# ESP-XBee.net
KiCad netlist of a schematic drawn in EAGLE
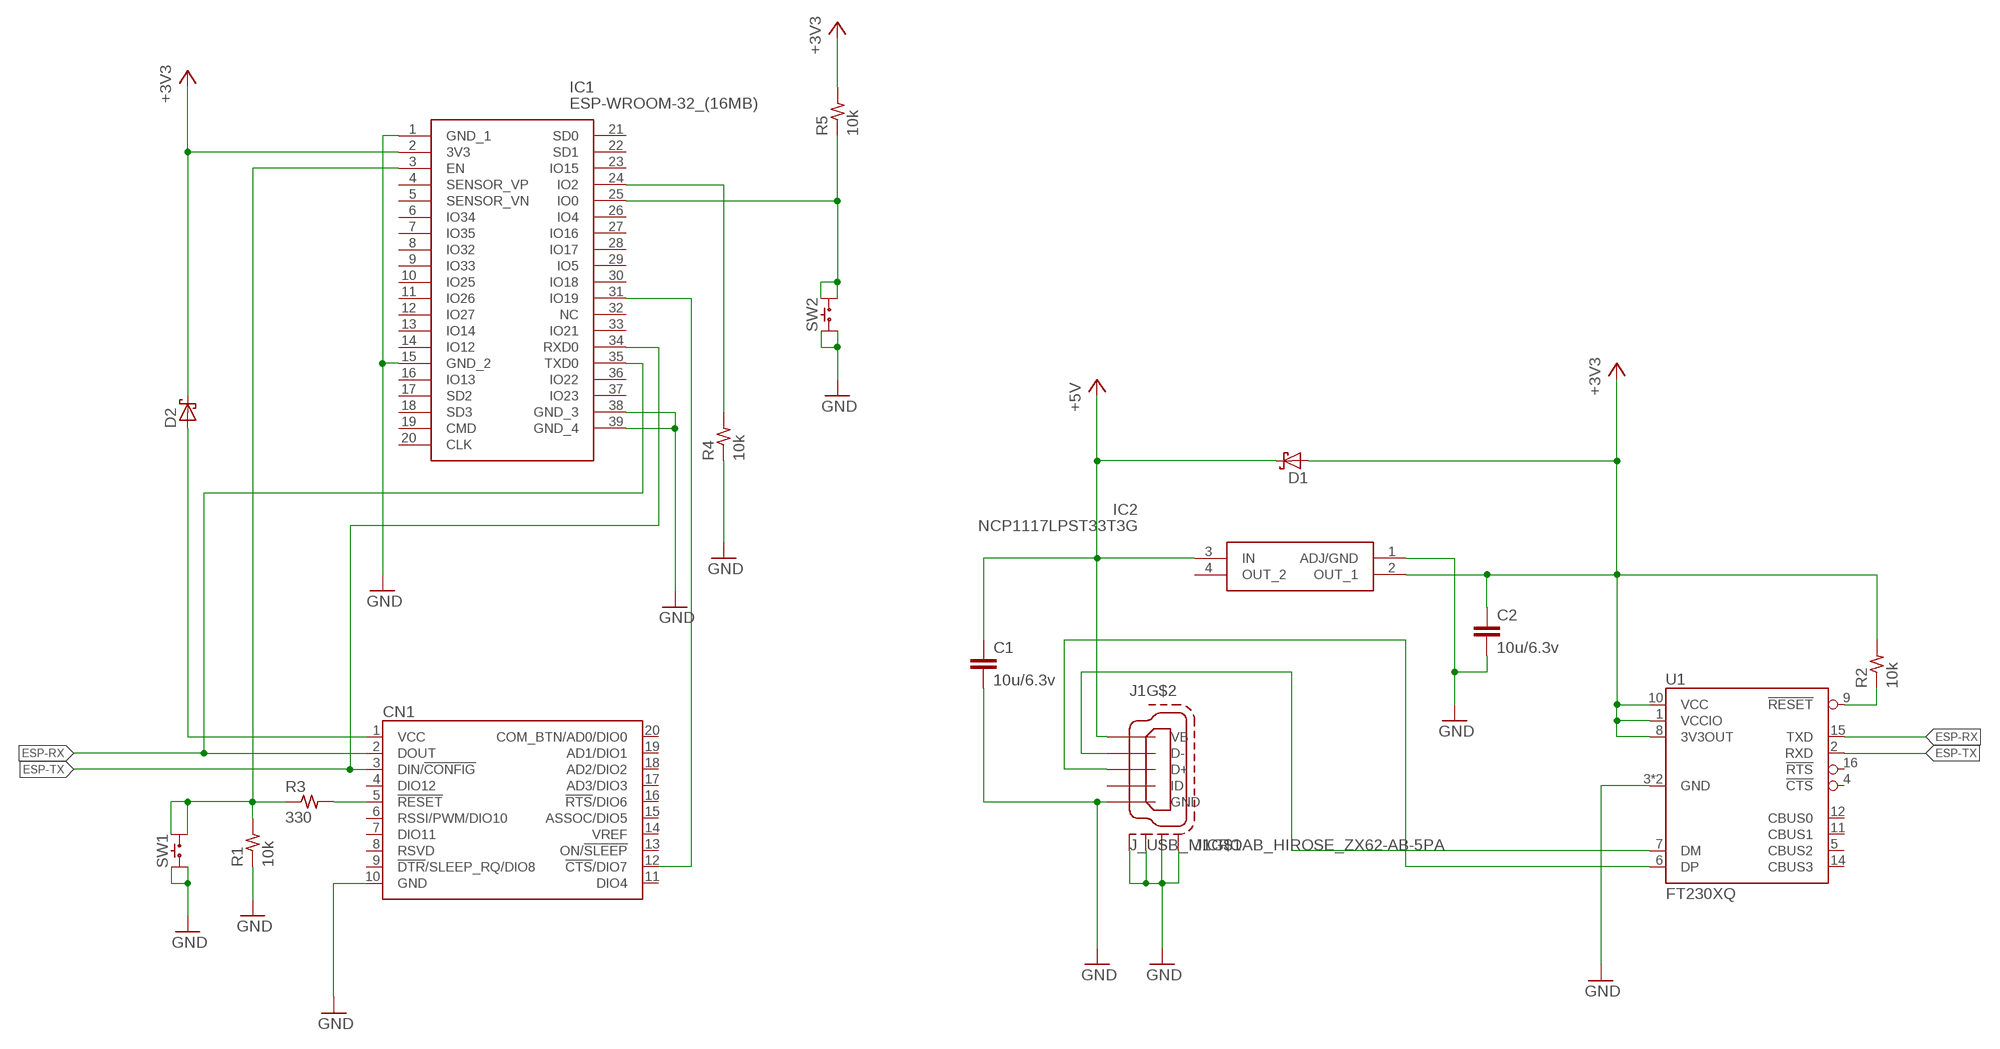
[diagram p0: schematic, sheet 1]

(export (version "E")
  (design (tool "Eeschema 10.0.6"))
  (components
    (comp (ref "C1")
      (value "10u/6.3v")
      (footprint "eagle-import:1005")
      (libsource (lib "eagle-import") (part "C1005"))
    )
    (comp (ref "C2")
      (value "10u/6.3v")
      (footprint "eagle-import:1005")
      (libsource (lib "eagle-import") (part "C1005"))
    )
    (comp (ref "CN1")
      (value "XBEE-TH")
      (footprint "eagle-import:XBEE-TH")
      (libsource (lib "eagle-import") (part "XBEE-TH"))
    )
    (comp (ref "D1")
      (value "SBD-SOD523")
      (footprint "eagle-import:SOD523")
      (libsource (lib "eagle-import") (part "SBD-SOD523"))
    )
    (comp (ref "D2")
      (value "SBD-SOD523")
      (footprint "eagle-import:SOD523")
      (libsource (lib "eagle-import") (part "SBD-SOD523"))
    )
    (comp (ref "IC1")
      (value "ESP-WROOM-32_(16MB)")
      (footprint "eagle-import:ESP32SOLO1")
      (fields (field (name "MANUFACTURER_PART_NUMBER") "ESP-WROOM-32 (16MB)"))
      (libsource (lib "eagle-import") (part "ESP-WROOM-32_(16MB)"))
    )
    (comp (ref "IC2")
      (value "NCP1117LPST33T3G")
      (footprint "eagle-import:SOT230P700X180-4N")
      (fields (field (name "RS_PART_NUMBER") "8022137P"))
      (libsource (lib "eagle-import") (part "NCP1117LPST33T3G"))
    )
    (comp (ref "J1")
      (value "J_USB_MICROAB_HIROSE_ZX62-AB-5PA")
      (footprint "eagle-import:J_USB_MICROAB_HIROSE_ZX62-AB-5PA")
      (libsource (lib "eagle-import") (part "J_USB_MICROAB_HIROSE_ZX62-AB-5PA"))
    )
    (comp (ref "R1")
      (value "10k")
      (footprint "eagle-import:1005")
      (libsource (lib "eagle-import") (part "R1005"))
    )
    (comp (ref "R2")
      (value "10k")
      (footprint "eagle-import:1005")
      (libsource (lib "eagle-import") (part "R1005"))
    )
    (comp (ref "R3")
      (value "330")
      (footprint "eagle-import:1005")
      (libsource (lib "eagle-import") (part "R1005"))
    )
    (comp (ref "R4")
      (value "10k")
      (footprint "eagle-import:1005")
      (libsource (lib "eagle-import") (part "R1005"))
    )
    (comp (ref "R5")
      (value "10k")
      (footprint "eagle-import:1005")
      (libsource (lib "eagle-import") (part "R1005"))
    )
    (comp (ref "SW1")
      (value "SKRP")
      (footprint "eagle-import:SKRP")
      (libsource (lib "eagle-import") (part "SKRP"))
    )
    (comp (ref "SW2")
      (value "SKRP")
      (footprint "eagle-import:SKRP")
      (libsource (lib "eagle-import") (part "SKRP"))
    )
    (comp (ref "U1")
      (value "FT230XQ")
      (footprint "eagle-import:QFN16-0.65-NOPAD")
      (libsource (lib "eagle-import") (part "FT230XQ"))
    )
  )
  (nets
    (net (code "1") (name "+3V3") (class "Default")
      (node (ref "C2") (pin "1") (pinfunction "1_1") (pintype "passive"))
      (node (ref "D1") (pin "A") (pinfunction "A_A") (pintype "passive"))
      (node (ref "D2") (pin "K") (pinfunction "K_K") (pintype "passive"))
      (node (ref "IC1") (pin "2") (pinfunction "3V3_2") (pintype "bidirectional"))
      (node (ref "IC2") (pin "2") (pinfunction "OUT_1_2") (pintype "output"))
      (node (ref "R2") (pin "2") (pinfunction "2_2") (pintype "passive"))
      (node (ref "R5") (pin "2") (pinfunction "2_2") (pintype "passive"))
      (node (ref "U1") (pin "1") (pinfunction "VCCIO_1") (pintype "bidirectional"))
      (node (ref "U1") (pin "10") (pinfunction "VCC_10") (pintype "bidirectional"))
      (node (ref "U1") (pin "8") (pinfunction "3V3OUT_8") (pintype "bidirectional"))
    )
    (net (code "2") (name "+5V") (class "Default")
      (node (ref "C1") (pin "1") (pinfunction "1_1") (pintype "passive"))
      (node (ref "D1") (pin "K") (pinfunction "K_K") (pintype "passive"))
      (node (ref "IC2") (pin "3") (pinfunction "IN_3") (pintype "input"))
      (node (ref "J1") (pin "P$1") (pinfunction "VB_P$1") (pintype "passive"))
    )
    (net (code "3") (name "ESP-RX") (class "Default")
      (node (ref "CN1") (pin "2") (pinfunction "DOUT_2") (pintype "bidirectional"))
      (node (ref "IC1") (pin "35") (pinfunction "TXD0_35") (pintype "bidirectional"))
      (node (ref "U1") (pin "15") (pinfunction "TXD_15") (pintype "bidirectional"))
    )
    (net (code "4") (name "ESP-TX") (class "Default")
      (node (ref "CN1") (pin "3") (pinfunction "DIN/~{CONFIG}_3") (pintype "bidirectional"))
      (node (ref "IC1") (pin "34") (pinfunction "RXD0_34") (pintype "bidirectional"))
      (node (ref "U1") (pin "2") (pinfunction "RXD_2") (pintype "bidirectional"))
    )
    (net (code "5") (name "GND") (class "Default")
      (node (ref "C1") (pin "2") (pinfunction "2_2") (pintype "passive"))
      (node (ref "C2") (pin "2") (pinfunction "2_2") (pintype "passive"))
      (node (ref "CN1") (pin "10") (pinfunction "GND_10") (pintype "bidirectional"))
      (node (ref "IC1") (pin "1") (pinfunction "GND_1_1") (pintype "bidirectional"))
      (node (ref "IC1") (pin "15") (pinfunction "GND_2_15") (pintype "bidirectional"))
      (node (ref "IC1") (pin "38") (pinfunction "GND_3_38") (pintype "bidirectional"))
      (node (ref "IC1") (pin "39") (pinfunction "GND_4_39") (pintype "bidirectional"))
      (node (ref "IC2") (pin "1") (pinfunction "ADJ/GND_1") (pintype "power_in"))
      (node (ref "J1") (pin "P$5") (pinfunction "GND_P$5") (pintype "passive"))
      (node (ref "J1") (pin "SHIELD1") (pinfunction "S1_SHIELD1") (pintype "passive"))
      (node (ref "J1") (pin "SHIELD2") (pinfunction "S2_SHIELD2") (pintype "passive"))
      (node (ref "J1") (pin "SHIELD3") (pinfunction "S3_SHIELD3") (pintype "passive"))
      (node (ref "J1") (pin "SHIELD4") (pinfunction "S4_SHIELD4") (pintype "passive"))
      (node (ref "R1") (pin "1") (pinfunction "1_1") (pintype "passive"))
      (node (ref "R4") (pin "1") (pinfunction "1_1") (pintype "passive"))
      (node (ref "SW1") (pin "A1") (pinfunction "A1_A1") (pintype "passive"))
      (node (ref "SW1") (pin "A2") (pinfunction "A2_A2") (pintype "passive"))
      (node (ref "SW2") (pin "A1") (pinfunction "A1_A1") (pintype "passive"))
      (node (ref "SW2") (pin "A2") (pinfunction "A2_A2") (pintype "passive"))
      (node (ref "U1") (pin "13") (pinfunction "GND_13") (pintype "bidirectional"))
      (node (ref "U1") (pin "3") (pinfunction "GND_3") (pintype "bidirectional"))
    )
    (net (code "6") (name "Net-(CN1-VCC)") (class "Default")
      (node (ref "CN1") (pin "1") (pinfunction "VCC_1") (pintype "bidirectional"))
      (node (ref "D2") (pin "A") (pinfunction "A_A") (pintype "passive"))
    )
    (net (code "7") (name "Net-(CN1-~{CTS}{slash}DIO7)") (class "Default")
      (node (ref "CN1") (pin "12") (pinfunction "~{CTS}/DIO7_12") (pintype "bidirectional"))
      (node (ref "IC1") (pin "31") (pinfunction "IO19_31") (pintype "bidirectional"))
    )
    (net (code "8") (name "Net-(CN1-~{RESET})") (class "Default")
      (node (ref "CN1") (pin "5") (pinfunction "~{RESET}_5") (pintype "bidirectional"))
      (node (ref "R3") (pin "2") (pinfunction "2_2") (pintype "passive"))
    )
    (net (code "9") (name "Net-(IC1-EN)") (class "Default")
      (node (ref "IC1") (pin "3") (pinfunction "EN_3") (pintype "bidirectional"))
      (node (ref "R1") (pin "2") (pinfunction "2_2") (pintype "passive"))
      (node (ref "R3") (pin "1") (pinfunction "1_1") (pintype "passive"))
      (node (ref "SW1") (pin "B1") (pinfunction "B1_B1") (pintype "passive"))
      (node (ref "SW1") (pin "B2") (pinfunction "B2_B2") (pintype "passive"))
    )
    (net (code "10") (name "Net-(IC1-IO0)") (class "Default")
      (node (ref "IC1") (pin "25") (pinfunction "IO0_25") (pintype "bidirectional"))
      (node (ref "R5") (pin "1") (pinfunction "1_1") (pintype "passive"))
      (node (ref "SW2") (pin "B1") (pinfunction "B1_B1") (pintype "passive"))
      (node (ref "SW2") (pin "B2") (pinfunction "B2_B2") (pintype "passive"))
    )
    (net (code "11") (name "Net-(IC1-IO2)") (class "Default")
      (node (ref "IC1") (pin "24") (pinfunction "IO2_24") (pintype "bidirectional"))
      (node (ref "R4") (pin "2") (pinfunction "2_2") (pintype "passive"))
    )
    (net (code "12") (name "Net-(J1B-D+)") (class "Default")
      (node (ref "J1") (pin "P$3") (pinfunction "D+_P$3") (pintype "passive"))
      (node (ref "U1") (pin "6") (pinfunction "DP_6") (pintype "bidirectional"))
    )
    (net (code "13") (name "Net-(J1B-D-)") (class "Default")
      (node (ref "J1") (pin "P$2") (pinfunction "D-_P$2") (pintype "passive"))
      (node (ref "U1") (pin "7") (pinfunction "DM_7") (pintype "bidirectional"))
    )
    (net (code "14") (name "Net-(U1-~{RESET})") (class "Default")
      (node (ref "R2") (pin "1") (pinfunction "1_1") (pintype "passive"))
      (node (ref "U1") (pin "9") (pinfunction "~{RESET}_9") (pintype "bidirectional"))
    )
    (net (code "15") (name "unconnected-(CN1-AD1{slash}DIO1-Pad19)") (class "Default")
      (node (ref "CN1") (pin "19") (pinfunction "AD1/DIO1_19") (pintype "bidirectional"))
    )
    (net (code "16") (name "unconnected-(CN1-AD2{slash}DIO2-Pad18)") (class "Default")
      (node (ref "CN1") (pin "18") (pinfunction "AD2/DIO2_18") (pintype "bidirectional"))
    )
    (net (code "17") (name "unconnected-(CN1-AD3{slash}DIO3-Pad17)") (class "Default")
      (node (ref "CN1") (pin "17") (pinfunction "AD3/DIO3_17") (pintype "bidirectional"))
    )
    (net (code "18") (name "unconnected-(CN1-ASSOC{slash}DIO5-Pad15)") (class "Default")
      (node (ref "CN1") (pin "15") (pinfunction "ASSOC/DIO5_15") (pintype "bidirectional"))
    )
    (net (code "19") (name "unconnected-(CN1-COM_BTN{slash}AD0{slash}DIO0-Pad20)") (class "Default")
      (node (ref "CN1") (pin "20") (pinfunction "COM_BTN/AD0/DIO0_20") (pintype "bidirectional"))
    )
    (net (code "20") (name "unconnected-(CN1-DIO4-Pad11)") (class "Default")
      (node (ref "CN1") (pin "11") (pinfunction "DIO4_11") (pintype "bidirectional"))
    )
    (net (code "21") (name "unconnected-(CN1-DIO11-Pad7)") (class "Default")
      (node (ref "CN1") (pin "7") (pinfunction "DIO11_7") (pintype "bidirectional"))
    )
    (net (code "22") (name "unconnected-(CN1-DIO12-Pad4)") (class "Default")
      (node (ref "CN1") (pin "4") (pinfunction "DIO12_4") (pintype "bidirectional"))
    )
    (net (code "23") (name "unconnected-(CN1-ON{slash}~{SLEEP}-Pad13)") (class "Default")
      (node (ref "CN1") (pin "13") (pinfunction "ON/~{SLEEP}_13") (pintype "bidirectional"))
    )
    (net (code "24") (name "unconnected-(CN1-RSSI{slash}PWM{slash}DIO10-Pad6)") (class "Default")
      (node (ref "CN1") (pin "6") (pinfunction "RSSI/PWM/DIO10_6") (pintype "bidirectional"))
    )
    (net (code "25") (name "unconnected-(CN1-RSVD-Pad8)") (class "Default")
      (node (ref "CN1") (pin "8") (pinfunction "RSVD_8") (pintype "bidirectional"))
    )
    (net (code "26") (name "unconnected-(CN1-VREF-Pad14)") (class "Default")
      (node (ref "CN1") (pin "14") (pinfunction "VREF_14") (pintype "bidirectional"))
    )
    (net (code "27") (name "unconnected-(CN1-~{DTR}{slash}SLEEP_RQ{slash}DIO8-Pad9)") (class "Default")
      (node (ref "CN1") (pin "9") (pinfunction "~{DTR}/SLEEP_RQ/DIO8_9") (pintype "bidirectional"))
    )
    (net (code "28") (name "unconnected-(CN1-~{RTS}{slash}DIO6-Pad16)") (class "Default")
      (node (ref "CN1") (pin "16") (pinfunction "~{RTS}/DIO6_16") (pintype "bidirectional"))
    )
    (net (code "29") (name "unconnected-(IC1-CLK-Pad20)") (class "Default")
      (node (ref "IC1") (pin "20") (pinfunction "CLK_20") (pintype "bidirectional"))
    )
    (net (code "30") (name "unconnected-(IC1-CMD-Pad19)") (class "Default")
      (node (ref "IC1") (pin "19") (pinfunction "CMD_19") (pintype "bidirectional"))
    )
    (net (code "31") (name "unconnected-(IC1-IO4-Pad26)") (class "Default")
      (node (ref "IC1") (pin "26") (pinfunction "IO4_26") (pintype "bidirectional"))
    )
    (net (code "32") (name "unconnected-(IC1-IO5-Pad29)") (class "Default")
      (node (ref "IC1") (pin "29") (pinfunction "IO5_29") (pintype "bidirectional"))
    )
    (net (code "33") (name "unconnected-(IC1-IO12-Pad14)") (class "Default")
      (node (ref "IC1") (pin "14") (pinfunction "IO12_14") (pintype "bidirectional"))
    )
    (net (code "34") (name "unconnected-(IC1-IO13-Pad16)") (class "Default")
      (node (ref "IC1") (pin "16") (pinfunction "IO13_16") (pintype "bidirectional"))
    )
    (net (code "35") (name "unconnected-(IC1-IO14-Pad13)") (class "Default")
      (node (ref "IC1") (pin "13") (pinfunction "IO14_13") (pintype "bidirectional"))
    )
    (net (code "36") (name "unconnected-(IC1-IO15-Pad23)") (class "Default")
      (node (ref "IC1") (pin "23") (pinfunction "IO15_23") (pintype "bidirectional"))
    )
    (net (code "37") (name "unconnected-(IC1-IO16-Pad27)") (class "Default")
      (node (ref "IC1") (pin "27") (pinfunction "IO16_27") (pintype "bidirectional"))
    )
    (net (code "38") (name "unconnected-(IC1-IO17-Pad28)") (class "Default")
      (node (ref "IC1") (pin "28") (pinfunction "IO17_28") (pintype "bidirectional"))
    )
    (net (code "39") (name "unconnected-(IC1-IO18-Pad30)") (class "Default")
      (node (ref "IC1") (pin "30") (pinfunction "IO18_30") (pintype "bidirectional"))
    )
    (net (code "40") (name "unconnected-(IC1-IO21-Pad33)") (class "Default")
      (node (ref "IC1") (pin "33") (pinfunction "IO21_33") (pintype "bidirectional"))
    )
    (net (code "41") (name "unconnected-(IC1-IO22-Pad36)") (class "Default")
      (node (ref "IC1") (pin "36") (pinfunction "IO22_36") (pintype "bidirectional"))
    )
    (net (code "42") (name "unconnected-(IC1-IO23-Pad37)") (class "Default")
      (node (ref "IC1") (pin "37") (pinfunction "IO23_37") (pintype "bidirectional"))
    )
    (net (code "43") (name "unconnected-(IC1-IO25-Pad10)") (class "Default")
      (node (ref "IC1") (pin "10") (pinfunction "IO25_10") (pintype "bidirectional"))
    )
    (net (code "44") (name "unconnected-(IC1-IO26-Pad11)") (class "Default")
      (node (ref "IC1") (pin "11") (pinfunction "IO26_11") (pintype "bidirectional"))
    )
    (net (code "45") (name "unconnected-(IC1-IO27-Pad12)") (class "Default")
      (node (ref "IC1") (pin "12") (pinfunction "IO27_12") (pintype "bidirectional"))
    )
    (net (code "46") (name "unconnected-(IC1-IO32-Pad8)") (class "Default")
      (node (ref "IC1") (pin "8") (pinfunction "IO32_8") (pintype "bidirectional"))
    )
    (net (code "47") (name "unconnected-(IC1-IO33-Pad9)") (class "Default")
      (node (ref "IC1") (pin "9") (pinfunction "IO33_9") (pintype "bidirectional"))
    )
    (net (code "48") (name "unconnected-(IC1-IO34-Pad6)") (class "Default")
      (node (ref "IC1") (pin "6") (pinfunction "IO34_6") (pintype "bidirectional"))
    )
    (net (code "49") (name "unconnected-(IC1-IO35-Pad7)") (class "Default")
      (node (ref "IC1") (pin "7") (pinfunction "IO35_7") (pintype "bidirectional"))
    )
    (net (code "50") (name "unconnected-(IC1-NC-Pad32)") (class "Default")
      (node (ref "IC1") (pin "32") (pinfunction "NC_32") (pintype "no_connect"))
    )
    (net (code "51") (name "unconnected-(IC1-SD0-Pad21)") (class "Default")
      (node (ref "IC1") (pin "21") (pinfunction "SD0_21") (pintype "bidirectional"))
    )
    (net (code "52") (name "unconnected-(IC1-SD1-Pad22)") (class "Default")
      (node (ref "IC1") (pin "22") (pinfunction "SD1_22") (pintype "bidirectional"))
    )
    (net (code "53") (name "unconnected-(IC1-SD2-Pad17)") (class "Default")
      (node (ref "IC1") (pin "17") (pinfunction "SD2_17") (pintype "bidirectional"))
    )
    (net (code "54") (name "unconnected-(IC1-SD3-Pad18)") (class "Default")
      (node (ref "IC1") (pin "18") (pinfunction "SD3_18") (pintype "bidirectional"))
    )
    (net (code "55") (name "unconnected-(IC1-SENSOR_VN-Pad5)") (class "Default")
      (node (ref "IC1") (pin "5") (pinfunction "SENSOR_VN_5") (pintype "bidirectional"))
    )
    (net (code "56") (name "unconnected-(IC1-SENSOR_VP-Pad4)") (class "Default")
      (node (ref "IC1") (pin "4") (pinfunction "SENSOR_VP_4") (pintype "bidirectional"))
    )
    (net (code "57") (name "unconnected-(IC2-OUT_2-Pad4)") (class "Default")
      (node (ref "IC2") (pin "4") (pinfunction "OUT_2_4") (pintype "output"))
    )
    (net (code "58") (name "unconnected-(J1B-ID-PadP$4)") (class "Default")
      (node (ref "J1") (pin "P$4") (pinfunction "ID_P$4") (pintype "passive"))
    )
    (net (code "59") (name "unconnected-(U1-CBUS0-Pad12)") (class "Default")
      (node (ref "U1") (pin "12") (pinfunction "CBUS0_12") (pintype "bidirectional"))
    )
    (net (code "60") (name "unconnected-(U1-CBUS1-Pad11)") (class "Default")
      (node (ref "U1") (pin "11") (pinfunction "CBUS1_11") (pintype "bidirectional"))
    )
    (net (code "61") (name "unconnected-(U1-CBUS2-Pad5)") (class "Default")
      (node (ref "U1") (pin "5") (pinfunction "CBUS2_5") (pintype "bidirectional"))
    )
    (net (code "62") (name "unconnected-(U1-CBUS3-Pad14)") (class "Default")
      (node (ref "U1") (pin "14") (pinfunction "CBUS3_14") (pintype "bidirectional"))
    )
    (net (code "63") (name "unconnected-(U1-~{CTS}-Pad4)") (class "Default")
      (node (ref "U1") (pin "4") (pinfunction "~{CTS}_4") (pintype "bidirectional"))
    )
    (net (code "64") (name "unconnected-(U1-~{RTS}-Pad16)") (class "Default")
      (node (ref "U1") (pin "16") (pinfunction "~{RTS}_16") (pintype "bidirectional"))
    )
  )
)
